# CH32F203C8U6-R0.net
KiCad netlist of a schematic drawn in Altium Designer
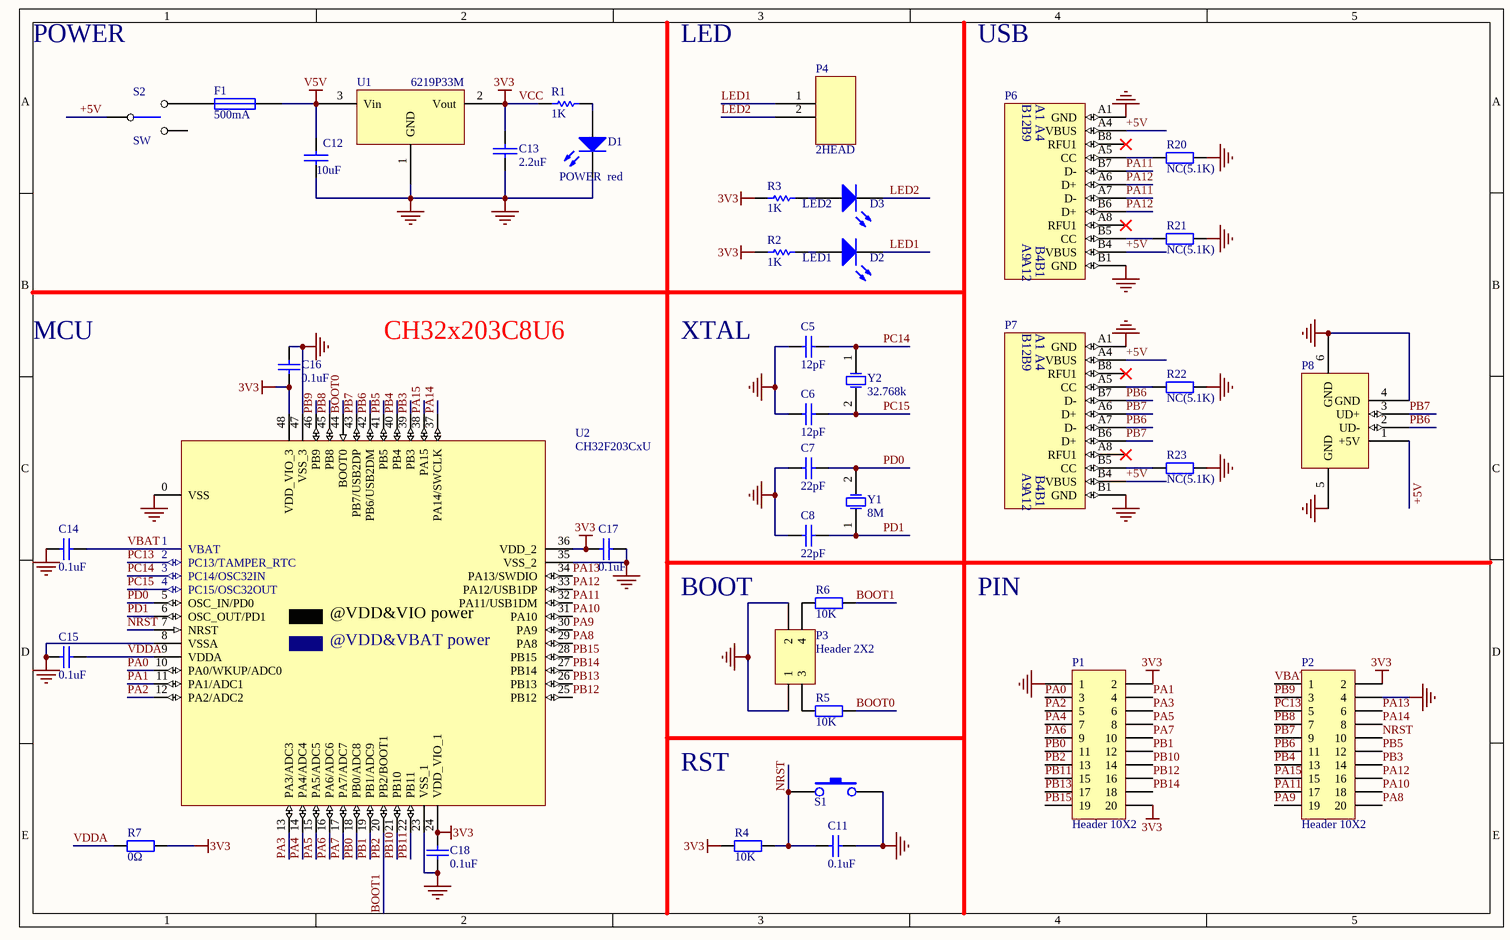
[diagram p0: CH32F203C8U6-R0.SchDoc]

(export (version "E")
  (design (tool "Eeschema 10.0.6"))
  (components
    (comp (ref "C5")
      (value "12pF")
      (footprint "0603")
      (description "Capacitor")
      (fields (field (name "PUBLISHER") "Altium Limited"))
      (libsource (lib "*") (part "Cap"))
    )
    (comp (ref "C6")
      (value "12pF")
      (footprint "0603")
      (description "Capacitor")
      (fields (field (name "PUBLISHER") "Altium Limited"))
      (libsource (lib "*") (part "Cap"))
    )
    (comp (ref "C7")
      (value "22pF")
      (footprint "0603")
      (description "Capacitor")
      (fields (field (name "PUBLISHER") "Altium Limited"))
      (libsource (lib "*") (part "Cap"))
    )
    (comp (ref "C8")
      (value "22pF")
      (footprint "0603")
      (description "Capacitor")
      (fields (field (name "PUBLISHER") "Altium Limited"))
      (libsource (lib "*") (part "Cap"))
    )
    (comp (ref "C11")
      (value "0.1uF")
      (footprint "0603")
      (description "Capacitor")
      (fields (field (name "PUBLISHER") "Altium Limited"))
      (libsource (lib "*") (part "Cap"))
    )
    (comp (ref "C12")
      (value "10uF")
      (footprint "3216")
      (description "Capacitor")
      (libsource (lib "*") (part "CAP"))
    )
    (comp (ref "C13")
      (value "2.2uF")
      (footprint "0603")
      (description "Capacitor")
      (libsource (lib "*") (part "CAP"))
    )
    (comp (ref "C14")
      (value "0.1uF")
      (footprint "0603")
      (description "Capacitor")
      (fields (field (name "PUBLISHER") "Altium Limited"))
      (libsource (lib "*") (part "Cap"))
    )
    (comp (ref "C15")
      (value "0.1uF")
      (footprint "0603")
      (description "Capacitor")
      (fields (field (name "PUBLISHER") "Altium Limited"))
      (libsource (lib "*") (part "Cap"))
    )
    (comp (ref "C16")
      (value "0.1uF")
      (footprint "0603")
      (description "Capacitor")
      (fields (field (name "PUBLISHER") "Altium Limited"))
      (libsource (lib "*") (part "Cap"))
    )
    (comp (ref "C17")
      (value "0.1uF")
      (footprint "0603")
      (description "Capacitor")
      (fields (field (name "PUBLISHER") "Altium Limited"))
      (libsource (lib "*") (part "Cap"))
    )
    (comp (ref "C18")
      (value "0.1uF")
      (footprint "0603")
      (description "Capacitor")
      (fields (field (name "PUBLISHER") "Altium Limited"))
      (libsource (lib "*") (part "Cap"))
    )
    (comp (ref "D1")
      (value "POWER  red")
      (footprint "0603L")
      (description "Typical INFRARED GaAs LED")
      (fields (field (name "PUBLISHER") "Altium Limited"))
      (libsource (lib "*") (part "LED0"))
    )
    (comp (ref "D2")
      (value "LED1")
      (footprint "0603L")
      (description "Typical INFRARED GaAs LED")
      (fields (field (name "PUBLISHER") "Altium Limited"))
      (libsource (lib "*") (part "LED0"))
    )
    (comp (ref "D3")
      (value "LED2")
      (footprint "0603L")
      (description "Typical INFRARED GaAs LED")
      (fields (field (name "PUBLISHER") "Altium Limited"))
      (libsource (lib "*") (part "LED0"))
    )
    (comp (ref "F1")
      (value "500mA")
      (footprint "0603")
      (description "Fuse")
      (libsource (lib "*") (part "FUSE1"))
    )
    (comp (ref "P1")
      (value "Header 10X2")
      (footprint "IDC20")
      (description "Header, 10-Pin, Dual row")
      (fields (field (name "PUBLISHER") "Altium Limited"))
      (libsource (lib "*") (part "Header 10X2"))
    )
    (comp (ref "P2")
      (value "Header 10X2")
      (footprint "IDC20")
      (description "Header, 10-Pin, Dual row")
      (fields (field (name "PUBLISHER") "Altium Limited"))
      (libsource (lib "*") (part "Header 10X2"))
    )
    (comp (ref "P3")
      (value "Header 2X2")
      (footprint "HDR2X2")
      (description "Header, 2-Pin, Dual row")
      (fields (field (name "PUBLISHER") "Altium Limited"))
      (libsource (lib "*") (part "Header 2X2"))
    )
    (comp (ref "P4") (value "2HEAD") (footprint "SIP2 - 40mil") (libsource (lib "*") (part "2HEAD")))
    (comp (ref "P6")
      (value "TYPE-C")
      (footprint "TYPE-C-Receptacle-2.0")
      (libsource (lib "*") (part "TYPE-C1"))
    )
    (comp (ref "P7")
      (value "TYPE-C")
      (footprint "TYPE-C-Receptacle-2.0")
      (libsource (lib "*") (part "TYPE-C1"))
    )
    (comp (ref "P8")
      (value "USB_A")
      (footprint "USBA-L")
      (description "USB Port")
      (libsource (lib "*") (part "USB"))
    )
    (comp (ref "R1")
      (value "1K")
      (footprint "0603")
      (description "Semiconductor Resistor")
      (fields (field (name "PUBLISHER") "Altium Limited"))
      (libsource (lib "*") (part "Res Semi"))
    )
    (comp (ref "R2")
      (value "1K")
      (footprint "0603")
      (description "Semiconductor Resistor")
      (fields (field (name "PUBLISHER") "Altium Limited"))
      (libsource (lib "*") (part "Res Semi"))
    )
    (comp (ref "R3")
      (value "1K")
      (footprint "0603")
      (description "Semiconductor Resistor")
      (fields (field (name "PUBLISHER") "Altium Limited"))
      (libsource (lib "*") (part "Res Semi"))
    )
    (comp (ref "R4")
      (value "10K")
      (footprint "0603")
      (description "Resistor")
      (fields (field (name "PUBLISHER") "Altium Limited"))
      (libsource (lib "*") (part "Res2"))
    )
    (comp (ref "R5")
      (value "10K")
      (footprint "0603")
      (description "Resistor")
      (fields (field (name "PUBLISHER") "Altium Limited"))
      (libsource (lib "*") (part "Res2"))
    )
    (comp (ref "R6")
      (value "10K")
      (footprint "0603")
      (description "Resistor")
      (fields (field (name "PUBLISHER") "Altium Limited"))
      (libsource (lib "*") (part "Res2"))
    )
    (comp (ref "R7")
      (value "0Ω")
      (footprint "0603")
      (description "Resistor")
      (fields (field (name "PUBLISHER") "Altium Limited"))
      (libsource (lib "*") (part "Res2"))
    )
    (comp (ref "R20")
      (value "NC(5.1K)")
      (footprint "0603")
      (description "Resistor")
      (libsource (lib "Miscellaneous Devices") (part "Res2"))
    )
    (comp (ref "R21")
      (value "NC(5.1K)")
      (footprint "0603")
      (description "Resistor")
      (libsource (lib "Miscellaneous Devices") (part "Res2"))
    )
    (comp (ref "R22")
      (value "NC(5.1K)")
      (footprint "0603")
      (description "Resistor")
      (libsource (lib "Miscellaneous Devices") (part "Res2"))
    )
    (comp (ref "R23")
      (value "NC(5.1K)")
      (footprint "0603")
      (description "Resistor")
      (libsource (lib "Miscellaneous Devices") (part "Res2"))
    )
    (comp (ref "S1") (value "KEY") (footprint "贴片按键") (libsource (lib "*") (part "KEY")))
    (comp (ref "S2") (value "SW") (footprint "KEY2") (libsource (lib "*") (part "SW")))
    (comp (ref "U1")
      (value "6219P33M")
      (footprint "SOT-23")
      (libsource (lib "wch_sch_others") (part "6219P33M"))
    )
    (comp (ref "U2")
      (value "CH32F203CxU")
      (footprint "QFN48_7X7")
      (description "ARM M3 LMD-MCU, 144MHz, 2*USB FS, CAN")
      (libsource (lib "CHXXX") (part "CH32F203CxU"))
    )
    (comp (ref "Y1")
      (value "8M")
      (footprint "XT62/28")
      (description "Crystal Oscillator")
      (fields (field (name "PUBLISHER") "Altium Limited"))
      (libsource (lib "*") (part "XTAL"))
    )
    (comp (ref "Y2")
      (value "32.768k")
      (footprint "FC-135")
      (description "Crystal Oscillator")
      (fields (field (name "PUBLISHER") "Altium Limited"))
      (libsource (lib "*") (part "XTAL"))
    )
  )
  (nets
    (net (code "1") (name "/+5V") (class "Default")
      (node (ref "P6") (pin "A4") (pinfunction "VBUS_A4") (pintype "bidirectional"))
      (node (ref "P6") (pin "B4") (pinfunction "VBUS_B4") (pintype "bidirectional"))
      (node (ref "P7") (pin "A4") (pinfunction "VBUS_A4") (pintype "bidirectional"))
      (node (ref "P7") (pin "B4") (pinfunction "VBUS_B4") (pintype "bidirectional"))
      (node (ref "P8") (pin "1") (pinfunction "+5V_1") (pintype "power_in"))
      (node (ref "S2") (pin "1") (pinfunction "1_1") (pintype "passive"))
    )
    (net (code "3") (name "/BOOT0") (class "Default")
      (node (ref "R5") (pin "1") (pinfunction "1_1") (pintype "passive"))
      (node (ref "U2") (pin "44") (pinfunction "BOOT0_44") (pintype "input"))
    )
    (net (code "4") (name "/BOOT1") (class "Default")
      (node (ref "P1") (pin "13") (pinfunction "13_13") (pintype "passive"))
      (node (ref "R6") (pin "1") (pinfunction "1_1") (pintype "passive"))
      (node (ref "U2") (pin "20") (pinfunction "PB2/BOOT1_20") (pintype "bidirectional"))
    )
    (net (code "5") (name "/LED1") (class "Default")
      (node (ref "D2") (pin "2") (pinfunction "K_2") (pintype "passive"))
      (node (ref "P4") (pin "1") (pintype "passive"))
    )
    (net (code "6") (name "/LED2") (class "Default")
      (node (ref "D3") (pin "2") (pinfunction "K_2") (pintype "passive"))
      (node (ref "P4") (pin "2") (pintype "passive"))
    )
    (net (code "7") (name "/NRST") (class "Default")
      (node (ref "C11") (pin "2") (pinfunction "2_2") (pintype "passive"))
      (node (ref "P2") (pin "10") (pinfunction "10_10") (pintype "passive"))
      (node (ref "R4") (pin "1") (pinfunction "1_1") (pintype "passive"))
      (node (ref "S1") (pin "1") (pinfunction "1_1") (pintype "passive"))
      (node (ref "U2") (pin "7") (pinfunction "NRST_7") (pintype "input"))
    )
    (net (code "8") (name "/PA0") (class "Default")
      (node (ref "P1") (pin "3") (pinfunction "3_3") (pintype "passive"))
      (node (ref "U2") (pin "10") (pinfunction "PA0/WKUP/ADC0_10") (pintype "bidirectional"))
    )
    (net (code "9") (name "/PA1") (class "Default")
      (node (ref "P1") (pin "4") (pinfunction "4_4") (pintype "passive"))
      (node (ref "U2") (pin "11") (pinfunction "PA1/ADC1_11") (pintype "bidirectional"))
    )
    (net (code "10") (name "/PA2") (class "Default")
      (node (ref "P1") (pin "5") (pinfunction "5_5") (pintype "passive"))
      (node (ref "U2") (pin "12") (pinfunction "PA2/ADC2_12") (pintype "bidirectional"))
    )
    (net (code "11") (name "/PA3") (class "Default")
      (node (ref "P1") (pin "6") (pinfunction "6_6") (pintype "passive"))
      (node (ref "U2") (pin "13") (pinfunction "PA3/ADC3_13") (pintype "bidirectional"))
    )
    (net (code "12") (name "/PA4") (class "Default")
      (node (ref "P1") (pin "7") (pinfunction "7_7") (pintype "passive"))
      (node (ref "U2") (pin "14") (pinfunction "PA4/ADC4_14") (pintype "bidirectional"))
    )
    (net (code "13") (name "/PA5") (class "Default")
      (node (ref "P1") (pin "8") (pinfunction "8_8") (pintype "passive"))
      (node (ref "U2") (pin "15") (pinfunction "PA5/ADC5_15") (pintype "bidirectional"))
    )
    (net (code "14") (name "/PA6") (class "Default")
      (node (ref "P1") (pin "9") (pinfunction "9_9") (pintype "passive"))
      (node (ref "U2") (pin "16") (pinfunction "PA6/ADC6_16") (pintype "bidirectional"))
    )
    (net (code "15") (name "/PA7") (class "Default")
      (node (ref "P1") (pin "10") (pinfunction "10_10") (pintype "passive"))
      (node (ref "U2") (pin "17") (pinfunction "PA7/ADC7_17") (pintype "bidirectional"))
    )
    (net (code "16") (name "/PA8") (class "Default")
      (node (ref "P2") (pin "20") (pinfunction "20_20") (pintype "passive"))
      (node (ref "U2") (pin "29") (pinfunction "PA8_29") (pintype "bidirectional"))
    )
    (net (code "17") (name "/PA9") (class "Default")
      (node (ref "P2") (pin "19") (pinfunction "19_19") (pintype "passive"))
      (node (ref "U2") (pin "30") (pinfunction "PA9_30") (pintype "bidirectional"))
    )
    (net (code "18") (name "/PA10") (class "Default")
      (node (ref "P2") (pin "18") (pinfunction "18_18") (pintype "passive"))
      (node (ref "U2") (pin "31") (pinfunction "PA10_31") (pintype "bidirectional"))
    )
    (net (code "19") (name "/PA11") (class "Default")
      (node (ref "P2") (pin "17") (pinfunction "17_17") (pintype "passive"))
      (node (ref "P6") (pin "A7") (pinfunction "D-_A7") (pintype "bidirectional"))
      (node (ref "P6") (pin "B7") (pinfunction "D-_B7") (pintype "bidirectional"))
      (node (ref "U2") (pin "32") (pinfunction "PA11/USB1DM_32") (pintype "bidirectional"))
    )
    (net (code "20") (name "/PA12") (class "Default")
      (node (ref "P2") (pin "16") (pinfunction "16_16") (pintype "passive"))
      (node (ref "P6") (pin "A6") (pinfunction "D+_A6") (pintype "bidirectional"))
      (node (ref "P6") (pin "B6") (pinfunction "D+_B6") (pintype "bidirectional"))
      (node (ref "U2") (pin "33") (pinfunction "PA12/USB1DP_33") (pintype "bidirectional"))
    )
    (net (code "21") (name "/PA13") (class "Default")
      (node (ref "P2") (pin "6") (pinfunction "6_6") (pintype "passive"))
      (node (ref "U2") (pin "34") (pinfunction "PA13/SWDIO_34") (pintype "bidirectional"))
    )
    (net (code "22") (name "/PA14") (class "Default")
      (node (ref "P2") (pin "8") (pinfunction "8_8") (pintype "passive"))
      (node (ref "U2") (pin "37") (pinfunction "PA14/SWCLK_37") (pintype "bidirectional"))
    )
    (net (code "23") (name "/PA15") (class "Default")
      (node (ref "P2") (pin "15") (pinfunction "15_15") (pintype "passive"))
      (node (ref "U2") (pin "38") (pinfunction "PA15_38") (pintype "bidirectional"))
    )
    (net (code "24") (name "/PB0") (class "Default")
      (node (ref "P1") (pin "11") (pinfunction "11_11") (pintype "passive"))
      (node (ref "U2") (pin "18") (pinfunction "PB0/ADC8_18") (pintype "bidirectional"))
    )
    (net (code "25") (name "/PB1") (class "Default")
      (node (ref "P1") (pin "12") (pinfunction "12_12") (pintype "passive"))
      (node (ref "U2") (pin "19") (pinfunction "PB1/ADC9_19") (pintype "bidirectional"))
    )
    (net (code "26") (name "/PB3") (class "Default")
      (node (ref "P2") (pin "14") (pinfunction "14_14") (pintype "passive"))
      (node (ref "U2") (pin "39") (pinfunction "PB3_39") (pintype "bidirectional"))
    )
    (net (code "27") (name "/PB4") (class "Default")
      (node (ref "P2") (pin "13") (pinfunction "13_13") (pintype "passive"))
      (node (ref "U2") (pin "40") (pinfunction "PB4_40") (pintype "bidirectional"))
    )
    (net (code "28") (name "/PB5") (class "Default")
      (node (ref "P2") (pin "12") (pinfunction "12_12") (pintype "passive"))
      (node (ref "U2") (pin "41") (pinfunction "PB5_41") (pintype "bidirectional"))
    )
    (net (code "29") (name "/PB6") (class "Default")
      (node (ref "P2") (pin "11") (pinfunction "11_11") (pintype "passive"))
      (node (ref "P7") (pin "A7") (pinfunction "D-_A7") (pintype "bidirectional"))
      (node (ref "P7") (pin "B7") (pinfunction "D-_B7") (pintype "bidirectional"))
      (node (ref "P8") (pin "2") (pinfunction "UD-_2") (pintype "bidirectional"))
      (node (ref "U2") (pin "42") (pinfunction "PB6/USB2DM_42") (pintype "bidirectional"))
    )
    (net (code "30") (name "/PB7") (class "Default")
      (node (ref "P2") (pin "9") (pinfunction "9_9") (pintype "passive"))
      (node (ref "P7") (pin "A6") (pinfunction "D+_A6") (pintype "bidirectional"))
      (node (ref "P7") (pin "B6") (pinfunction "D+_B6") (pintype "bidirectional"))
      (node (ref "P8") (pin "3") (pinfunction "UD+_3") (pintype "bidirectional"))
      (node (ref "U2") (pin "43") (pinfunction "PB7/USB2DP_43") (pintype "bidirectional"))
    )
    (net (code "31") (name "/PB8") (class "Default")
      (node (ref "P2") (pin "7") (pinfunction "7_7") (pintype "passive"))
      (node (ref "U2") (pin "45") (pinfunction "PB8_45") (pintype "bidirectional"))
    )
    (net (code "32") (name "/PB9") (class "Default")
      (node (ref "P2") (pin "3") (pinfunction "3_3") (pintype "passive"))
      (node (ref "U2") (pin "46") (pinfunction "PB9_46") (pintype "bidirectional"))
    )
    (net (code "33") (name "/PB10") (class "Default")
      (node (ref "P1") (pin "14") (pinfunction "14_14") (pintype "passive"))
      (node (ref "U2") (pin "21") (pinfunction "PB10_21") (pintype "bidirectional"))
    )
    (net (code "34") (name "/PB11") (class "Default")
      (node (ref "P1") (pin "15") (pinfunction "15_15") (pintype "passive"))
      (node (ref "U2") (pin "22") (pinfunction "PB11_22") (pintype "bidirectional"))
    )
    (net (code "35") (name "/PB12") (class "Default")
      (node (ref "P1") (pin "16") (pinfunction "16_16") (pintype "passive"))
      (node (ref "U2") (pin "25") (pinfunction "PB12_25") (pintype "bidirectional"))
    )
    (net (code "36") (name "/PB13") (class "Default")
      (node (ref "P1") (pin "17") (pinfunction "17_17") (pintype "passive"))
      (node (ref "U2") (pin "26") (pinfunction "PB13_26") (pintype "bidirectional"))
    )
    (net (code "37") (name "/PB14") (class "Default")
      (node (ref "P1") (pin "18") (pinfunction "18_18") (pintype "passive"))
      (node (ref "U2") (pin "27") (pinfunction "PB14_27") (pintype "bidirectional"))
    )
    (net (code "38") (name "/PB15") (class "Default")
      (node (ref "P1") (pin "19") (pinfunction "19_19") (pintype "passive"))
      (node (ref "U2") (pin "28") (pinfunction "PB15_28") (pintype "bidirectional"))
    )
    (net (code "39") (name "/PC13") (class "Default")
      (node (ref "P2") (pin "5") (pinfunction "5_5") (pintype "passive"))
      (node (ref "U2") (pin "2") (pinfunction "PC13/TAMPER_RTC_2") (pintype "bidirectional"))
    )
    (net (code "40") (name "/PC14") (class "Default")
      (node (ref "C5") (pin "1") (pinfunction "1_1") (pintype "passive"))
      (node (ref "U2") (pin "3") (pinfunction "PC14/OSC32IN_3") (pintype "bidirectional"))
      (node (ref "Y2") (pin "1") (pinfunction "OSC1_1") (pintype "passive"))
    )
    (net (code "41") (name "/PC15") (class "Default")
      (node (ref "C6") (pin "1") (pinfunction "1_1") (pintype "passive"))
      (node (ref "U2") (pin "4") (pinfunction "PC15/OSC32OUT_4") (pintype "bidirectional"))
      (node (ref "Y2") (pin "2") (pinfunction "OSC2_2") (pintype "passive"))
    )
    (net (code "42") (name "/PD0") (class "Default")
      (node (ref "C7") (pin "2") (pinfunction "2_2") (pintype "passive"))
      (node (ref "U2") (pin "5") (pinfunction "OSC_IN/PD0_5") (pintype "bidirectional"))
      (node (ref "Y1") (pin "2") (pinfunction "OSC2_2") (pintype "passive"))
    )
    (net (code "43") (name "/PD1") (class "Default")
      (node (ref "C8") (pin "2") (pinfunction "2_2") (pintype "passive"))
      (node (ref "U2") (pin "6") (pinfunction "OSC_OUT/PD1_6") (pintype "bidirectional"))
      (node (ref "Y1") (pin "1") (pinfunction "OSC1_1") (pintype "passive"))
    )
    (net (code "44") (name "/VBAT") (class "Default")
      (node (ref "C14") (pin "1") (pinfunction "1_1") (pintype "passive"))
      (node (ref "P2") (pin "1") (pinfunction "1_1") (pintype "passive"))
      (node (ref "U2") (pin "1") (pinfunction "VBAT_1") (pintype "power_in"))
    )
    (net (code "45") (name "/VDDA") (class "Default")
      (node (ref "C15") (pin "1") (pinfunction "1_1") (pintype "passive"))
      (node (ref "R7") (pin "2") (pinfunction "2_2") (pintype "passive"))
      (node (ref "U2") (pin "9") (pinfunction "VDDA_9") (pintype "power_in"))
    )
    (net (code "46") (name "3V3") (class "Default")
      (node (ref "C13") (pin "1") (pinfunction "1_1") (pintype "passive"))
      (node (ref "C16") (pin "2") (pinfunction "2_2") (pintype "passive"))
      (node (ref "C17") (pin "2") (pinfunction "2_2") (pintype "passive"))
      (node (ref "C18") (pin "2") (pinfunction "2_2") (pintype "passive"))
      (node (ref "P1") (pin "2") (pinfunction "2_2") (pintype "passive"))
      (node (ref "P1") (pin "20") (pinfunction "20_20") (pintype "passive"))
      (node (ref "P2") (pin "2") (pinfunction "2_2") (pintype "passive"))
      (node (ref "R1") (pin "2") (pinfunction "2_2") (pintype "passive"))
      (node (ref "R2") (pin "1") (pinfunction "1_1") (pintype "passive"))
      (node (ref "R3") (pin "1") (pinfunction "1_1") (pintype "passive"))
      (node (ref "R4") (pin "2") (pinfunction "2_2") (pintype "passive"))
      (node (ref "R7") (pin "1") (pinfunction "1_1") (pintype "passive"))
      (node (ref "U1") (pin "2") (pinfunction "Vout_2") (pintype "passive"))
      (node (ref "U2") (pin "24") (pinfunction "VDD_VIO_1_24") (pintype "power_in"))
      (node (ref "U2") (pin "36") (pinfunction "VDD_2_36") (pintype "power_in"))
      (node (ref "U2") (pin "48") (pinfunction "VDD_VIO_3_48") (pintype "power_in"))
    )
    (net (code "47") (name "GND") (class "Default")
      (node (ref "C11") (pin "1") (pinfunction "1_1") (pintype "passive"))
      (node (ref "C12") (pin "2") (pinfunction "2_2") (pintype "passive"))
      (node (ref "C13") (pin "2") (pinfunction "2_2") (pintype "passive"))
      (node (ref "C14") (pin "2") (pinfunction "2_2") (pintype "passive"))
      (node (ref "C15") (pin "2") (pinfunction "2_2") (pintype "passive"))
      (node (ref "C16") (pin "1") (pinfunction "1_1") (pintype "passive"))
      (node (ref "C17") (pin "1") (pinfunction "1_1") (pintype "passive"))
      (node (ref "C18") (pin "1") (pinfunction "1_1") (pintype "passive"))
      (node (ref "C5") (pin "2") (pinfunction "2_2") (pintype "passive"))
      (node (ref "C6") (pin "2") (pinfunction "2_2") (pintype "passive"))
      (node (ref "C7") (pin "1") (pinfunction "1_1") (pintype "passive"))
      (node (ref "C8") (pin "1") (pinfunction "1_1") (pintype "passive"))
      (node (ref "D1") (pin "2") (pinfunction "K_2") (pintype "passive"))
      (node (ref "P1") (pin "1") (pinfunction "1_1") (pintype "passive"))
      (node (ref "P2") (pin "4") (pinfunction "4_4") (pintype "passive"))
      (node (ref "P3") (pin "1") (pinfunction "1_1") (pintype "passive"))
      (node (ref "P3") (pin "2") (pinfunction "2_2") (pintype "passive"))
      (node (ref "P6") (pin "A1") (pinfunction "GND_A1") (pintype "bidirectional"))
      (node (ref "P6") (pin "B1") (pinfunction "GND_B1") (pintype "bidirectional"))
      (node (ref "P7") (pin "A1") (pinfunction "GND_A1") (pintype "bidirectional"))
      (node (ref "P7") (pin "B1") (pinfunction "GND_B1") (pintype "bidirectional"))
      (node (ref "P8") (pin "4") (pinfunction "GND_4") (pintype "power_in"))
      (node (ref "P8") (pin "5") (pinfunction "GND_5") (pintype "power_in"))
      (node (ref "P8") (pin "6") (pinfunction "GND_6") (pintype "power_in"))
      (node (ref "R20") (pin "2") (pinfunction "2_2") (pintype "passive"))
      (node (ref "R21") (pin "2") (pinfunction "2_2") (pintype "passive"))
      (node (ref "R22") (pin "2") (pinfunction "2_2") (pintype "passive"))
      (node (ref "R23") (pin "2") (pinfunction "2_2") (pintype "passive"))
      (node (ref "S1") (pin "3") (pinfunction "3_3") (pintype "passive"))
      (node (ref "U1") (pin "1") (pinfunction "GND_1") (pintype "passive"))
      (node (ref "U2") (pin "0") (pinfunction "VSS_0") (pintype "power_in"))
      (node (ref "U2") (pin "23") (pinfunction "VSS_1_23") (pintype "power_in"))
      (node (ref "U2") (pin "35") (pinfunction "VSS_2_35") (pintype "power_in"))
      (node (ref "U2") (pin "47") (pinfunction "VSS_3_47") (pintype "power_in"))
      (node (ref "U2") (pin "8") (pinfunction "VSSA_8") (pintype "power_in"))
    )
    (net (code "48") (name "Net-(D1-A)") (class "Default")
      (node (ref "D1") (pin "1") (pinfunction "A_1") (pintype "passive"))
      (node (ref "R1") (pin "1") (pinfunction "1_1") (pintype "passive"))
    )
    (net (code "49") (name "Net-(D2-A)") (class "Default")
      (node (ref "D2") (pin "1") (pinfunction "A_1") (pintype "passive"))
      (node (ref "R2") (pin "2") (pinfunction "2_2") (pintype "passive"))
    )
    (net (code "50") (name "Net-(D3-A)") (class "Default")
      (node (ref "D3") (pin "1") (pinfunction "A_1") (pintype "passive"))
      (node (ref "R3") (pin "2") (pinfunction "2_2") (pintype "passive"))
    )
    (net (code "51") (name "Net-(F1-Pad1)") (class "Default")
      (node (ref "F1") (pin "1") (pinfunction "1_1") (pintype "passive"))
      (node (ref "S2") (pin "3") (pinfunction "3_3") (pintype "passive"))
    )
    (net (code "52") (name "Net-(P3-Pad3)") (class "Default")
      (node (ref "P3") (pin "3") (pinfunction "3_3") (pintype "passive"))
      (node (ref "R5") (pin "2") (pinfunction "2_2") (pintype "passive"))
    )
    (net (code "53") (name "Net-(P3-Pad4)") (class "Default")
      (node (ref "P3") (pin "4") (pinfunction "4_4") (pintype "passive"))
      (node (ref "R6") (pin "2") (pinfunction "2_2") (pintype "passive"))
    )
    (net (code "54") (name "Net-(P6-CC-PadA5)") (class "Default")
      (node (ref "P6") (pin "A5") (pinfunction "CC_A5") (pintype "bidirectional"))
      (node (ref "R20") (pin "1") (pinfunction "1_1") (pintype "passive"))
    )
    (net (code "55") (name "Net-(P6-CC-PadB5)") (class "Default")
      (node (ref "P6") (pin "B5") (pinfunction "CC_B5") (pintype "bidirectional"))
      (node (ref "R21") (pin "1") (pinfunction "1_1") (pintype "passive"))
    )
    (net (code "56") (name "Net-(P7-CC-PadA5)") (class "Default")
      (node (ref "P7") (pin "A5") (pinfunction "CC_A5") (pintype "bidirectional"))
      (node (ref "R22") (pin "1") (pinfunction "1_1") (pintype "passive"))
    )
    (net (code "57") (name "Net-(P7-CC-PadB5)") (class "Default")
      (node (ref "P7") (pin "B5") (pinfunction "CC_B5") (pintype "bidirectional"))
      (node (ref "R23") (pin "1") (pinfunction "1_1") (pintype "passive"))
    )
    (net (code "58") (name "V5V") (class "Default")
      (node (ref "C12") (pin "1") (pinfunction "1_1") (pintype "passive"))
      (node (ref "F1") (pin "2") (pinfunction "2_2") (pintype "passive"))
      (node (ref "U1") (pin "3") (pinfunction "Vin_3") (pintype "passive"))
    )
    (net (code "59") (name "unconnected-(P6-RFU1-PadA8)") (class "Default")
      (node (ref "P6") (pin "A8") (pinfunction "RFU1_A8") (pintype "bidirectional+no_connect"))
    )
    (net (code "60") (name "unconnected-(P6-RFU1-PadB8)") (class "Default")
      (node (ref "P6") (pin "B8") (pinfunction "RFU1_B8") (pintype "bidirectional+no_connect"))
    )
    (net (code "61") (name "unconnected-(P7-RFU1-PadA8)") (class "Default")
      (node (ref "P7") (pin "A8") (pinfunction "RFU1_A8") (pintype "bidirectional+no_connect"))
    )
    (net (code "62") (name "unconnected-(P7-RFU1-PadB8)") (class "Default")
      (node (ref "P7") (pin "B8") (pinfunction "RFU1_B8") (pintype "bidirectional+no_connect"))
    )
    (net (code "63") (name "unconnected-(S2-Pad2)") (class "Default")
      (node (ref "S2") (pin "2") (pinfunction "2_2") (pintype "passive"))
    )
  )
)
